# GSMPart.net
KiCad netlist of a schematic drawn in Altium Designer
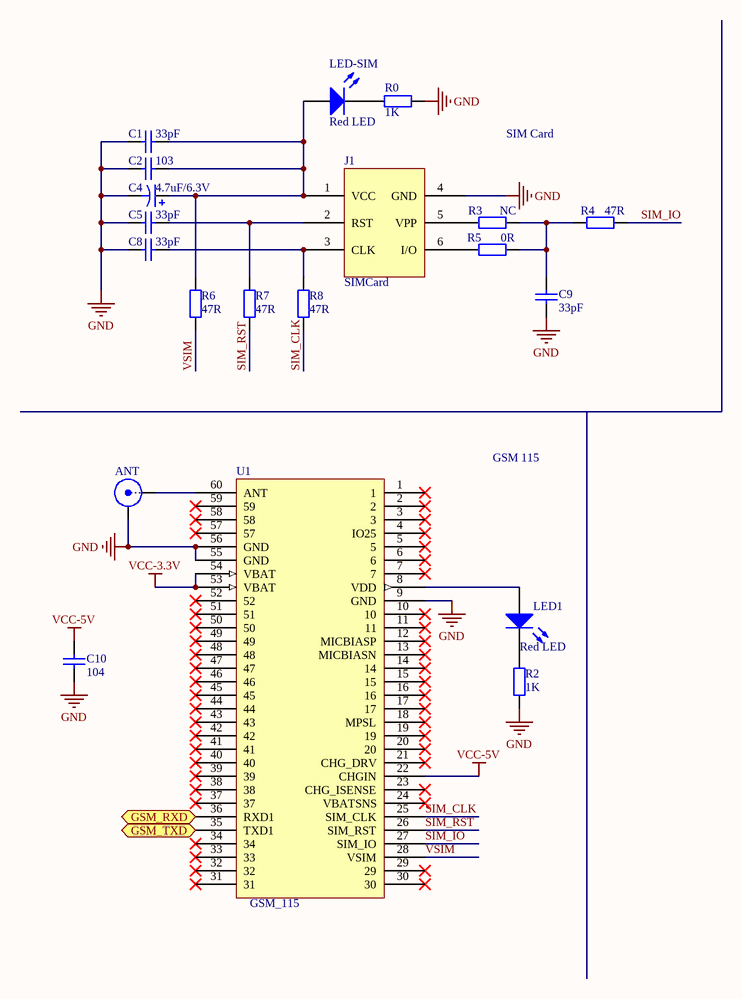
[diagram p0: GSMPart.SchDoc]

(export (version "E")
  (design (tool "Eeschema 10.0.6"))
  (components
    (comp (ref "ANT")
      (value "SMB")
      (footprint "SMB_V-RJ45")
      (description "SMB Straight Connector")
      (fields (field (name "PUBLISHER") "Altium Limited"))
      (libsource (lib "Miscellaneous Connectors") (part "SMB"))
    )
    (comp (ref "C1")
      (value "33pF")
      (footprint "1608[0603]")
      (description "Capacitor")
      (fields (field (name "Comment") "Cap") (field (name "PUBLISHER") "Altium Limited"))
      (libsource (lib "common") (part "Cap"))
    )
    (comp (ref "C2")
      (value "103")
      (footprint "1608[0603]")
      (description "Capacitor")
      (fields (field (name "Comment") "Cap") (field (name "PUBLISHER") "Altium Limited"))
      (libsource (lib "common") (part "Cap"))
    )
    (comp (ref "C4")
      (value "4.7uF/6.3V")
      (footprint "Standard:B")
      (description "Polarized Capacitor (Axial)")
      (fields (field (name "Comment") "CAP POL") (field (name "PUBLISHER") "Altium Limited"))
      (libsource (lib "common") (part "CAP POL"))
    )
    (comp (ref "C5")
      (value "33pF")
      (footprint "1608[0603]")
      (description "Capacitor")
      (fields (field (name "Comment") "Cap") (field (name "PUBLISHER") "Altium Limited"))
      (libsource (lib "common") (part "Cap"))
    )
    (comp (ref "C8")
      (value "33pF")
      (footprint "1608[0603]")
      (description "Capacitor")
      (fields (field (name "Comment") "Cap") (field (name "PUBLISHER") "Altium Limited"))
      (libsource (lib "common") (part "Cap"))
    )
    (comp (ref "C9")
      (value "33pF")
      (footprint "1608[0603]")
      (description "Capacitor")
      (fields (field (name "Comment") "Cap") (field (name "PUBLISHER") "Altium Limited"))
      (libsource (lib "common") (part "Cap"))
    )
    (comp (ref "C10")
      (value "104")
      (footprint "1608[0603]")
      (description "Capacitor")
      (fields (field (name "Comment") "Cap") (field (name "PUBLISHER") "Altium Limited"))
      (libsource (lib "common") (part "Cap"))
    )
    (comp (ref "J1")
      (value "SIMCard")
      (footprint "PCB_SIM")
      (description "Sim Card")
      (libsource (lib "*") (part "SIMCard"))
    )
    (comp (ref "LED-SIM")
      (value "Red LED")
      (footprint "2012[0805] - POL")
      (libsource (lib "common") (part "LED"))
    )
    (comp (ref "LED1")
      (value "Red LED")
      (footprint "2012[0805] - POL")
      (libsource (lib "common") (part "LED"))
    )
    (comp (ref "R0")
      (value "1K")
      (footprint "1608[0603]")
      (description "Resistor")
      (fields (field (name "Comment") "RES") (field (name "PUBLISHER") "Altium Limited"))
      (libsource (lib "common") (part "RES"))
    )
    (comp (ref "R2")
      (value "1K")
      (footprint "1608[0603]")
      (description "Resistor")
      (fields (field (name "Comment") "RES") (field (name "PUBLISHER") "Altium Limited"))
      (libsource (lib "") (part "RES_1"))
    )
    (comp (ref "R3")
      (value "NC")
      (footprint "1608[0603]")
      (description "Resistor")
      (fields (field (name "Comment") "RES") (field (name "PUBLISHER") "Altium Limited"))
      (libsource (lib "") (part "RES_2"))
    )
    (comp (ref "R4")
      (value "47R")
      (footprint "1608[0603]")
      (description "Resistor")
      (fields (field (name "Comment") "RES") (field (name "PUBLISHER") "Altium Limited"))
      (libsource (lib "") (part "RES_2"))
    )
    (comp (ref "R5")
      (value "0R")
      (footprint "1608[0603]")
      (description "Resistor")
      (fields (field (name "Comment") "RES") (field (name "PUBLISHER") "Altium Limited"))
      (libsource (lib "") (part "RES_2"))
    )
    (comp (ref "R6")
      (value "47R")
      (footprint "1608[0603]")
      (description "Resistor")
      (fields (field (name "Comment") "RES") (field (name "PUBLISHER") "Altium Limited"))
      (libsource (lib "") (part "RES_1"))
    )
    (comp (ref "R7")
      (value "47R")
      (footprint "1608[0603]")
      (description "Resistor")
      (fields (field (name "Comment") "RES") (field (name "PUBLISHER") "Altium Limited"))
      (libsource (lib "") (part "RES_1"))
    )
    (comp (ref "R8")
      (value "47R")
      (footprint "1608[0603]")
      (description "Resistor")
      (fields (field (name "Comment") "RES") (field (name "PUBLISHER") "Altium Limited"))
      (libsource (lib "") (part "RES_1"))
    )
    (comp (ref "U1") (value "GSM_115") (libsource (lib "GSM") (part "GSM115")))
  )
  (nets
    (net (code "1") (name "/GSM_RXD") (class "Default")
      (node (ref "U1") (pin "36") (pinfunction "RXD1_36") (pintype "passive"))
    )
    (net (code "2") (name "/GSM_TXD") (class "Default")
      (node (ref "U1") (pin "35") (pinfunction "TXD1_35") (pintype "passive"))
    )
    (net (code "3") (name "/SIM_CLK") (class "Default")
      (node (ref "R8") (pin "1") (pinfunction "1_1") (pintype "passive"))
      (node (ref "U1") (pin "25") (pinfunction "SIM_CLK_25") (pintype "passive"))
    )
    (net (code "4") (name "/SIM_IO") (class "Default")
      (node (ref "R4") (pin "2") (pinfunction "2_2") (pintype "passive"))
      (node (ref "U1") (pin "27") (pinfunction "SIM_IO_27") (pintype "passive"))
    )
    (net (code "5") (name "/SIM_RST") (class "Default")
      (node (ref "R7") (pin "1") (pinfunction "1_1") (pintype "passive"))
      (node (ref "U1") (pin "26") (pinfunction "SIM_RST_26") (pintype "passive"))
    )
    (net (code "6") (name "/VSIM") (class "Default")
      (node (ref "R6") (pin "1") (pinfunction "1_1") (pintype "passive"))
      (node (ref "U1") (pin "28") (pinfunction "VSIM_28") (pintype "passive"))
    )
    (net (code "7") (name "GND") (class "Default")
      (node (ref "ANT") (pin "2") (pinfunction "Y_2") (pintype "passive"))
      (node (ref "C1") (pin "1") (pinfunction "1_1") (pintype "passive"))
      (node (ref "C10") (pin "1") (pinfunction "1_1") (pintype "passive"))
      (node (ref "C2") (pin "1") (pinfunction "1_1") (pintype "passive"))
      (node (ref "C4") (pin "2") (pinfunction "2_2") (pintype "passive"))
      (node (ref "C5") (pin "1") (pinfunction "1_1") (pintype "passive"))
      (node (ref "C8") (pin "1") (pinfunction "1_1") (pintype "passive"))
      (node (ref "C9") (pin "1") (pinfunction "1_1") (pintype "passive"))
      (node (ref "J1") (pin "4") (pinfunction "GND_4") (pintype "passive"))
      (node (ref "R0") (pin "1") (pinfunction "1_1") (pintype "passive"))
      (node (ref "R2") (pin "1") (pinfunction "1_1") (pintype "passive"))
      (node (ref "U1") (pin "55") (pinfunction "GND_55") (pintype "passive"))
      (node (ref "U1") (pin "56") (pinfunction "GND_56") (pintype "passive"))
      (node (ref "U1") (pin "9") (pinfunction "GND_9") (pintype "passive"))
    )
    (net (code "8") (name "Net-(ANT-X)") (class "Default")
      (node (ref "ANT") (pin "1") (pinfunction "X_1") (pintype "passive"))
      (node (ref "U1") (pin "60") (pinfunction "ANT_60") (pintype "passive"))
    )
    (net (code "9") (name "Net-(C9-Pad2)") (class "Default")
      (node (ref "C9") (pin "2") (pinfunction "2_2") (pintype "passive"))
      (node (ref "R3") (pin "2") (pinfunction "2_2") (pintype "passive"))
      (node (ref "R4") (pin "1") (pinfunction "1_1") (pintype "passive"))
      (node (ref "R5") (pin "2") (pinfunction "2_2") (pintype "passive"))
    )
    (net (code "10") (name "Net-(J1-CLK)") (class "Default")
      (node (ref "C8") (pin "2") (pinfunction "2_2") (pintype "passive"))
      (node (ref "J1") (pin "3") (pinfunction "CLK_3") (pintype "passive"))
      (node (ref "R8") (pin "2") (pinfunction "2_2") (pintype "passive"))
    )
    (net (code "11") (name "Net-(J1-I{slash}O)") (class "Default")
      (node (ref "J1") (pin "6") (pinfunction "I/O_6") (pintype "passive"))
      (node (ref "R5") (pin "1") (pinfunction "1_1") (pintype "passive"))
    )
    (net (code "12") (name "Net-(J1-RST)") (class "Default")
      (node (ref "C5") (pin "2") (pinfunction "2_2") (pintype "passive"))
      (node (ref "J1") (pin "2") (pinfunction "RST_2") (pintype "passive"))
      (node (ref "R7") (pin "2") (pinfunction "2_2") (pintype "passive"))
    )
    (net (code "13") (name "Net-(J1-VCC)") (class "Default")
      (node (ref "C1") (pin "2") (pinfunction "2_2") (pintype "passive"))
      (node (ref "C2") (pin "2") (pinfunction "2_2") (pintype "passive"))
      (node (ref "C4") (pin "1") (pinfunction "1_1") (pintype "passive"))
      (node (ref "J1") (pin "1") (pinfunction "VCC_1") (pintype "passive"))
      (node (ref "LED-SIM") (pin "1") (pinfunction "A_1") (pintype "passive"))
      (node (ref "R6") (pin "2") (pinfunction "2_2") (pintype "passive"))
    )
    (net (code "14") (name "Net-(J1-VPP)") (class "Default")
      (node (ref "J1") (pin "5") (pinfunction "VPP_5") (pintype "passive"))
      (node (ref "R3") (pin "1") (pinfunction "1_1") (pintype "passive"))
    )
    (net (code "15") (name "Net-(LED-SIM-K)") (class "Default")
      (node (ref "LED-SIM") (pin "2") (pinfunction "K_2") (pintype "passive"))
      (node (ref "R0") (pin "2") (pinfunction "2_2") (pintype "passive"))
    )
    (net (code "16") (name "Net-(LED1-A)") (class "Default")
      (node (ref "LED1") (pin "1") (pinfunction "A_1") (pintype "passive"))
      (node (ref "U1") (pin "8") (pinfunction "VDD_8") (pintype "output"))
    )
    (net (code "17") (name "Net-(LED1-K)") (class "Default")
      (node (ref "LED1") (pin "2") (pinfunction "K_2") (pintype "passive"))
      (node (ref "R2") (pin "2") (pinfunction "2_2") (pintype "passive"))
    )
    (net (code "18") (name "VCC-3.3V") (class "Default")
      (node (ref "U1") (pin "53") (pinfunction "VBAT_53") (pintype "input"))
      (node (ref "U1") (pin "54") (pinfunction "VBAT_54") (pintype "input"))
    )
    (net (code "19") (name "VCC-5V") (class "Default")
      (node (ref "C10") (pin "2") (pinfunction "2_2") (pintype "passive"))
      (node (ref "U1") (pin "22") (pinfunction "CHGIN_22") (pintype "passive"))
    )
    (net (code "20") (name "unconnected-(U1-CHG_DRV-Pad21)") (class "Default")
      (node (ref "U1") (pin "21") (pinfunction "CHG_DRV_21") (pintype "passive+no_connect"))
    )
    (net (code "21") (name "unconnected-(U1-CHG_ISENSE-Pad23)") (class "Default")
      (node (ref "U1") (pin "23") (pinfunction "CHG_ISENSE_23") (pintype "passive+no_connect"))
    )
    (net (code "22") (name "unconnected-(U1-IO25-Pad4)") (class "Default")
      (node (ref "U1") (pin "4") (pinfunction "IO25_4") (pintype "passive+no_connect"))
    )
    (net (code "23") (name "unconnected-(U1-MICBIASN-Pad13)") (class "Default")
      (node (ref "U1") (pin "13") (pinfunction "MICBIASN_13") (pintype "passive+no_connect"))
    )
    (net (code "24") (name "unconnected-(U1-MICBIASP-Pad12)") (class "Default")
      (node (ref "U1") (pin "12") (pinfunction "MICBIASP_12") (pintype "passive+no_connect"))
    )
    (net (code "25") (name "unconnected-(U1-MPSL-Pad18)") (class "Default")
      (node (ref "U1") (pin "18") (pinfunction "MPSL_18") (pintype "passive+no_connect"))
    )
    (net (code "26") (name "unconnected-(U1-Pad1)") (class "Default")
      (node (ref "U1") (pin "1") (pinfunction "1_1") (pintype "passive+no_connect"))
    )
    (net (code "27") (name "unconnected-(U1-Pad2)") (class "Default")
      (node (ref "U1") (pin "2") (pinfunction "2_2") (pintype "passive+no_connect"))
    )
    (net (code "28") (name "unconnected-(U1-Pad3)") (class "Default")
      (node (ref "U1") (pin "3") (pinfunction "3_3") (pintype "passive+no_connect"))
    )
    (net (code "29") (name "unconnected-(U1-Pad5)") (class "Default")
      (node (ref "U1") (pin "5") (pinfunction "5_5") (pintype "passive+no_connect"))
    )
    (net (code "30") (name "unconnected-(U1-Pad6)") (class "Default")
      (node (ref "U1") (pin "6") (pinfunction "6_6") (pintype "passive+no_connect"))
    )
    (net (code "31") (name "unconnected-(U1-Pad7)") (class "Default")
      (node (ref "U1") (pin "7") (pinfunction "7_7") (pintype "passive+no_connect"))
    )
    (net (code "32") (name "unconnected-(U1-Pad10)") (class "Default")
      (node (ref "U1") (pin "10") (pinfunction "10_10") (pintype "passive+no_connect"))
    )
    (net (code "33") (name "unconnected-(U1-Pad11)") (class "Default")
      (node (ref "U1") (pin "11") (pinfunction "11_11") (pintype "passive+no_connect"))
    )
    (net (code "34") (name "unconnected-(U1-Pad14)") (class "Default")
      (node (ref "U1") (pin "14") (pinfunction "14_14") (pintype "passive+no_connect"))
    )
    (net (code "35") (name "unconnected-(U1-Pad15)") (class "Default")
      (node (ref "U1") (pin "15") (pinfunction "15_15") (pintype "passive+no_connect"))
    )
    (net (code "36") (name "unconnected-(U1-Pad16)") (class "Default")
      (node (ref "U1") (pin "16") (pinfunction "16_16") (pintype "passive+no_connect"))
    )
    (net (code "37") (name "unconnected-(U1-Pad17)") (class "Default")
      (node (ref "U1") (pin "17") (pinfunction "17_17") (pintype "passive+no_connect"))
    )
    (net (code "38") (name "unconnected-(U1-Pad19)") (class "Default")
      (node (ref "U1") (pin "19") (pinfunction "19_19") (pintype "passive+no_connect"))
    )
    (net (code "39") (name "unconnected-(U1-Pad20)") (class "Default")
      (node (ref "U1") (pin "20") (pinfunction "20_20") (pintype "passive+no_connect"))
    )
    (net (code "40") (name "unconnected-(U1-Pad29)") (class "Default")
      (node (ref "U1") (pin "29") (pinfunction "29_29") (pintype "passive+no_connect"))
    )
    (net (code "41") (name "unconnected-(U1-Pad30)") (class "Default")
      (node (ref "U1") (pin "30") (pinfunction "30_30") (pintype "passive+no_connect"))
    )
    (net (code "42") (name "unconnected-(U1-Pad31)") (class "Default")
      (node (ref "U1") (pin "31") (pinfunction "31_31") (pintype "passive+no_connect"))
    )
    (net (code "43") (name "unconnected-(U1-Pad32)") (class "Default")
      (node (ref "U1") (pin "32") (pinfunction "32_32") (pintype "passive+no_connect"))
    )
    (net (code "44") (name "unconnected-(U1-Pad33)") (class "Default")
      (node (ref "U1") (pin "33") (pinfunction "33_33") (pintype "passive+no_connect"))
    )
    (net (code "45") (name "unconnected-(U1-Pad34)") (class "Default")
      (node (ref "U1") (pin "34") (pinfunction "34_34") (pintype "passive+no_connect"))
    )
    (net (code "46") (name "unconnected-(U1-Pad37)") (class "Default")
      (node (ref "U1") (pin "37") (pinfunction "37_37") (pintype "passive+no_connect"))
    )
    (net (code "47") (name "unconnected-(U1-Pad38)") (class "Default")
      (node (ref "U1") (pin "38") (pinfunction "38_38") (pintype "passive+no_connect"))
    )
    (net (code "48") (name "unconnected-(U1-Pad39)") (class "Default")
      (node (ref "U1") (pin "39") (pinfunction "39_39") (pintype "passive+no_connect"))
    )
    (net (code "49") (name "unconnected-(U1-Pad40)") (class "Default")
      (node (ref "U1") (pin "40") (pinfunction "40_40") (pintype "passive+no_connect"))
    )
    (net (code "50") (name "unconnected-(U1-Pad41)") (class "Default")
      (node (ref "U1") (pin "41") (pinfunction "41_41") (pintype "passive+no_connect"))
    )
    (net (code "51") (name "unconnected-(U1-Pad42)") (class "Default")
      (node (ref "U1") (pin "42") (pinfunction "42_42") (pintype "passive+no_connect"))
    )
    (net (code "52") (name "unconnected-(U1-Pad43)") (class "Default")
      (node (ref "U1") (pin "43") (pinfunction "43_43") (pintype "passive+no_connect"))
    )
    (net (code "53") (name "unconnected-(U1-Pad44)") (class "Default")
      (node (ref "U1") (pin "44") (pinfunction "44_44") (pintype "passive+no_connect"))
    )
    (net (code "54") (name "unconnected-(U1-Pad45)") (class "Default")
      (node (ref "U1") (pin "45") (pinfunction "45_45") (pintype "passive+no_connect"))
    )
    (net (code "55") (name "unconnected-(U1-Pad46)") (class "Default")
      (node (ref "U1") (pin "46") (pinfunction "46_46") (pintype "passive+no_connect"))
    )
    (net (code "56") (name "unconnected-(U1-Pad47)") (class "Default")
      (node (ref "U1") (pin "47") (pinfunction "47_47") (pintype "passive+no_connect"))
    )
    (net (code "57") (name "unconnected-(U1-Pad48)") (class "Default")
      (node (ref "U1") (pin "48") (pinfunction "48_48") (pintype "passive+no_connect"))
    )
    (net (code "58") (name "unconnected-(U1-Pad49)") (class "Default")
      (node (ref "U1") (pin "49") (pinfunction "49_49") (pintype "passive+no_connect"))
    )
    (net (code "59") (name "unconnected-(U1-Pad50)") (class "Default")
      (node (ref "U1") (pin "50") (pinfunction "50_50") (pintype "passive+no_connect"))
    )
    (net (code "60") (name "unconnected-(U1-Pad51)") (class "Default")
      (node (ref "U1") (pin "51") (pinfunction "51_51") (pintype "passive+no_connect"))
    )
    (net (code "61") (name "unconnected-(U1-Pad52)") (class "Default")
      (node (ref "U1") (pin "52") (pinfunction "52_52") (pintype "passive+no_connect"))
    )
    (net (code "62") (name "unconnected-(U1-Pad57)") (class "Default")
      (node (ref "U1") (pin "57") (pinfunction "57_57") (pintype "passive+no_connect"))
    )
    (net (code "63") (name "unconnected-(U1-Pad58)") (class "Default")
      (node (ref "U1") (pin "58") (pinfunction "58_58") (pintype "passive+no_connect"))
    )
    (net (code "64") (name "unconnected-(U1-Pad59)") (class "Default")
      (node (ref "U1") (pin "59") (pinfunction "59_59") (pintype "passive+no_connect"))
    )
    (net (code "65") (name "unconnected-(U1-VBATSNS-Pad24)") (class "Default")
      (node (ref "U1") (pin "24") (pinfunction "VBATSNS_24") (pintype "passive+no_connect"))
    )
  )
)
